# HTDC.net
KiCad netlist of a schematic drawn in Altium Designer
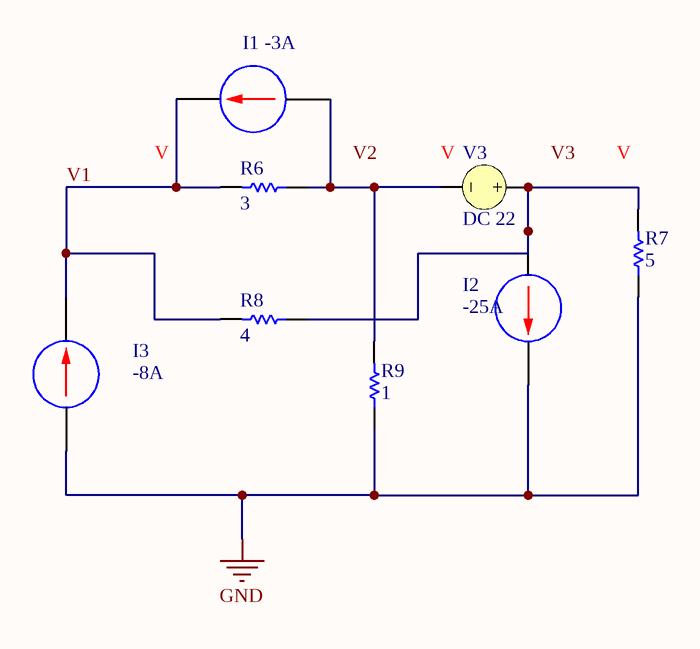
[diagram p0: HTDC.SchDoc]

(export (version "E")
  (design (tool "Eeschema 10.0.6"))
  (components
    (comp (ref "I1")
      (value "DC Current Source")
      (fields (field (name "DC") "-3A"))
      (libsource (lib "Simulation Generic Components") (part "DC Current Source"))
    )
    (comp (ref "I2")
      (value "DC Current Source")
      (fields (field (name "DC") "-25A"))
      (libsource (lib "Simulation Generic Components") (part "DC Current Source"))
    )
    (comp (ref "I3")
      (value "DC Current Source")
      (fields (field (name "DC") "-8A"))
      (libsource (lib "Simulation Generic Components") (part "DC Current Source"))
    )
    (comp (ref "R6")
      (value "3")
      (description "Resistor")
      (libsource (lib "Simulation Generic Components") (part "Resistor"))
    )
    (comp (ref "R7")
      (value "5")
      (description "Resistor")
      (libsource (lib "Simulation Generic Components") (part "Resistor"))
    )
    (comp (ref "R8")
      (value "4")
      (description "Resistor")
      (libsource (lib "Simulation Generic Components") (part "Resistor"))
    )
    (comp (ref "R9")
      (value "1")
      (description "Resistor")
      (libsource (lib "Simulation Generic Components") (part "Resistor"))
    )
    (comp (ref "V3")
      (value "DC 22")
      (description "Voltage Source")
      (fields (field (name "PUBLISHER") "Altium Limited"))
      (libsource (lib "Simulation Generic Components") (part "VSRC"))
    )
  )
  (nets
    (net (code "1") (name "/V1") (class "Default")
      (node (ref "I1") (pin "1") (pinfunction "+_1") (pintype "passive"))
      (node (ref "I3") (pin "1") (pinfunction "+_1") (pintype "passive"))
      (node (ref "R6") (pin "2") (pinfunction "2_2") (pintype "passive"))
      (node (ref "R8") (pin "2") (pinfunction "2_2") (pintype "passive"))
    )
    (net (code "4") (name "GND") (class "Default")
      (node (ref "I2") (pin "1") (pinfunction "+_1") (pintype "passive"))
      (node (ref "I3") (pin "2") (pinfunction "-_2") (pintype "passive"))
      (node (ref "R7") (pin "1") (pinfunction "1_1") (pintype "passive"))
      (node (ref "R9") (pin "1") (pinfunction "1_1") (pintype "passive"))
    )
    (net (code "5") (name "Net-(I1--)") (class "Default")
      (node (ref "I1") (pin "2") (pinfunction "-_2") (pintype "passive"))
      (node (ref "R6") (pin "1") (pinfunction "1_1") (pintype "passive"))
      (node (ref "R9") (pin "2") (pinfunction "2_2") (pintype "passive"))
      (node (ref "V3") (pin "2") (pinfunction "2_2") (pintype "passive"))
    )
    (net (code "6") (name "Net-(I2--)") (class "Default")
      (node (ref "I2") (pin "2") (pinfunction "-_2") (pintype "passive"))
      (node (ref "R7") (pin "2") (pinfunction "2_2") (pintype "passive"))
      (node (ref "R8") (pin "1") (pinfunction "1_1") (pintype "passive"))
      (node (ref "V3") (pin "1") (pinfunction "1_1") (pintype "passive"))
    )
  )
)
